# driver_motor_ver_2.net
KiCad netlist of a schematic drawn in EAGLE
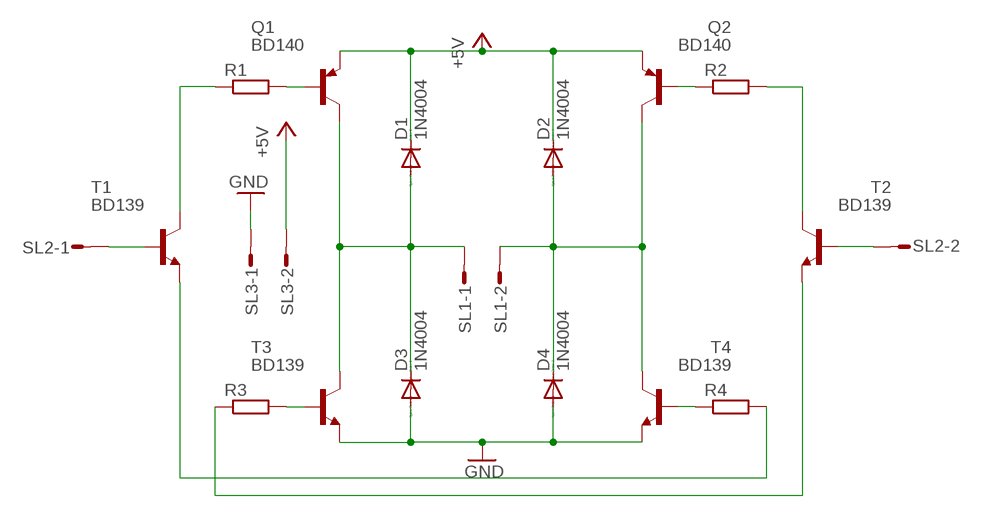
[diagram p0: schematic, sheet 1]

(export (version "E")
  (design (tool "Eeschema 10.0.6"))
  (components
    (comp (ref "D1")
      (value "1N4004")
      (footprint "eagle-import:DO41-10")
      (libsource (lib "eagle-import") (part "1N4004"))
    )
    (comp (ref "D2")
      (value "1N4004")
      (footprint "eagle-import:DO41-10")
      (libsource (lib "eagle-import") (part "1N4004"))
    )
    (comp (ref "D3")
      (value "1N4004")
      (footprint "eagle-import:DO41-10")
      (libsource (lib "eagle-import") (part "1N4004"))
    )
    (comp (ref "D4")
      (value "1N4004")
      (footprint "eagle-import:DO41-10")
      (libsource (lib "eagle-import") (part "1N4004"))
    )
    (comp (ref "Q1")
      (value "BD140")
      (footprint "eagle-import:TO126")
      (libsource (lib "eagle-import") (part "BD140"))
    )
    (comp (ref "Q2")
      (value "BD140")
      (footprint "eagle-import:TO126")
      (libsource (lib "eagle-import") (part "BD140"))
    )
    (comp (ref "R1")
      (value "R-EU_0204/5")
      (footprint "eagle-import:0204_5")
      (libsource (lib "eagle-import") (part "R-EU_0204/5"))
    )
    (comp (ref "R2")
      (value "R-EU_0204/5")
      (footprint "eagle-import:0204_5")
      (libsource (lib "eagle-import") (part "R-EU_0204/5"))
    )
    (comp (ref "R3")
      (value "R-EU_0204/5")
      (footprint "eagle-import:0204_5")
      (libsource (lib "eagle-import") (part "R-EU_0204/5"))
    )
    (comp (ref "R4")
      (value "R-EU_0204/5")
      (footprint "eagle-import:0204_5")
      (libsource (lib "eagle-import") (part "R-EU_0204/5"))
    )
    (comp (ref "SL1")
      (value "M02S")
      (footprint "eagle-import:02P")
      (libsource (lib "eagle-import") (part "M02S"))
    )
    (comp (ref "SL2")
      (value "M02S")
      (footprint "eagle-import:02P")
      (libsource (lib "eagle-import") (part "M02S"))
    )
    (comp (ref "SL3")
      (value "M02S")
      (footprint "eagle-import:02P")
      (libsource (lib "eagle-import") (part "M02S"))
    )
    (comp (ref "T1")
      (value "BD139")
      (footprint "eagle-import:TO126")
      (libsource (lib "eagle-import") (part "BD139"))
    )
    (comp (ref "T2")
      (value "BD139")
      (footprint "eagle-import:TO126")
      (libsource (lib "eagle-import") (part "BD139"))
    )
    (comp (ref "T3")
      (value "BD139")
      (footprint "eagle-import:TO126")
      (libsource (lib "eagle-import") (part "BD139"))
    )
    (comp (ref "T4")
      (value "BD139")
      (footprint "eagle-import:TO126")
      (libsource (lib "eagle-import") (part "BD139"))
    )
  )
  (nets
    (net (code "1") (name "+5V") (class "Default")
      (node (ref "D1") (pin "C") (pinfunction "C_C") (pintype "passive"))
      (node (ref "D2") (pin "C") (pinfunction "C_C") (pintype "passive"))
      (node (ref "Q1") (pin "1") (pinfunction "E_1") (pintype "passive"))
      (node (ref "Q2") (pin "1") (pinfunction "E_1") (pintype "passive"))
      (node (ref "SL3") (pin "2") (pinfunction "S_2") (pintype "passive"))
    )
    (net (code "2") (name "GND") (class "Default")
      (node (ref "D3") (pin "A") (pinfunction "A_A") (pintype "passive"))
      (node (ref "D4") (pin "A") (pinfunction "A_A") (pintype "passive"))
      (node (ref "SL3") (pin "1") (pinfunction "S_1") (pintype "passive"))
      (node (ref "T3") (pin "1") (pinfunction "E_1") (pintype "passive"))
      (node (ref "T4") (pin "1") (pinfunction "E_1") (pintype "passive"))
    )
    (net (code "3") (name "Net-(Q1-B)") (class "Default")
      (node (ref "Q1") (pin "3") (pinfunction "B_3") (pintype "passive"))
      (node (ref "R1") (pin "2") (pinfunction "2_2") (pintype "passive"))
    )
    (net (code "4") (name "Net-(Q1-C)") (class "Default")
      (node (ref "D1") (pin "A") (pinfunction "A_A") (pintype "passive"))
      (node (ref "D3") (pin "C") (pinfunction "C_C") (pintype "passive"))
      (node (ref "Q1") (pin "2") (pinfunction "C_2") (pintype "passive"))
      (node (ref "SL1") (pin "1") (pinfunction "S_1") (pintype "passive"))
      (node (ref "T3") (pin "2") (pinfunction "C_2") (pintype "passive"))
    )
    (net (code "5") (name "Net-(Q2-B)") (class "Default")
      (node (ref "Q2") (pin "3") (pinfunction "B_3") (pintype "passive"))
      (node (ref "R2") (pin "1") (pinfunction "1_1") (pintype "passive"))
    )
    (net (code "6") (name "Net-(Q2-C)") (class "Default")
      (node (ref "D2") (pin "A") (pinfunction "A_A") (pintype "passive"))
      (node (ref "D4") (pin "C") (pinfunction "C_C") (pintype "passive"))
      (node (ref "Q2") (pin "2") (pinfunction "C_2") (pintype "passive"))
      (node (ref "SL1") (pin "2") (pinfunction "S_2") (pintype "passive"))
      (node (ref "T4") (pin "2") (pinfunction "C_2") (pintype "passive"))
    )
    (net (code "7") (name "Net-(SL2A-S)") (class "Default")
      (node (ref "SL2") (pin "1") (pinfunction "S_1") (pintype "passive"))
      (node (ref "T1") (pin "3") (pinfunction "B_3") (pintype "passive"))
    )
    (net (code "8") (name "Net-(SL2B-S)") (class "Default")
      (node (ref "SL2") (pin "2") (pinfunction "S_2") (pintype "passive"))
      (node (ref "T2") (pin "3") (pinfunction "B_3") (pintype "passive"))
    )
    (net (code "9") (name "Net-(T1-C)") (class "Default")
      (node (ref "R1") (pin "1") (pinfunction "1_1") (pintype "passive"))
      (node (ref "T1") (pin "2") (pinfunction "C_2") (pintype "passive"))
    )
    (net (code "10") (name "Net-(T1-E)") (class "Default")
      (node (ref "R4") (pin "2") (pinfunction "2_2") (pintype "passive"))
      (node (ref "T1") (pin "1") (pinfunction "E_1") (pintype "passive"))
    )
    (net (code "11") (name "Net-(T2-C)") (class "Default")
      (node (ref "R2") (pin "2") (pinfunction "2_2") (pintype "passive"))
      (node (ref "T2") (pin "2") (pinfunction "C_2") (pintype "passive"))
    )
    (net (code "12") (name "Net-(T2-E)") (class "Default")
      (node (ref "R3") (pin "1") (pinfunction "1_1") (pintype "passive"))
      (node (ref "T2") (pin "1") (pinfunction "E_1") (pintype "passive"))
    )
    (net (code "13") (name "Net-(T3-B)") (class "Default")
      (node (ref "R3") (pin "2") (pinfunction "2_2") (pintype "passive"))
      (node (ref "T3") (pin "3") (pinfunction "B_3") (pintype "passive"))
    )
    (net (code "14") (name "Net-(T4-B)") (class "Default")
      (node (ref "R4") (pin "1") (pinfunction "1_1") (pintype "passive"))
      (node (ref "T4") (pin "3") (pinfunction "B_3") (pintype "passive"))
    )
  )
)
